# NodeMCU_AQM-4.net
KiCad netlist of a schematic drawn in EAGLE
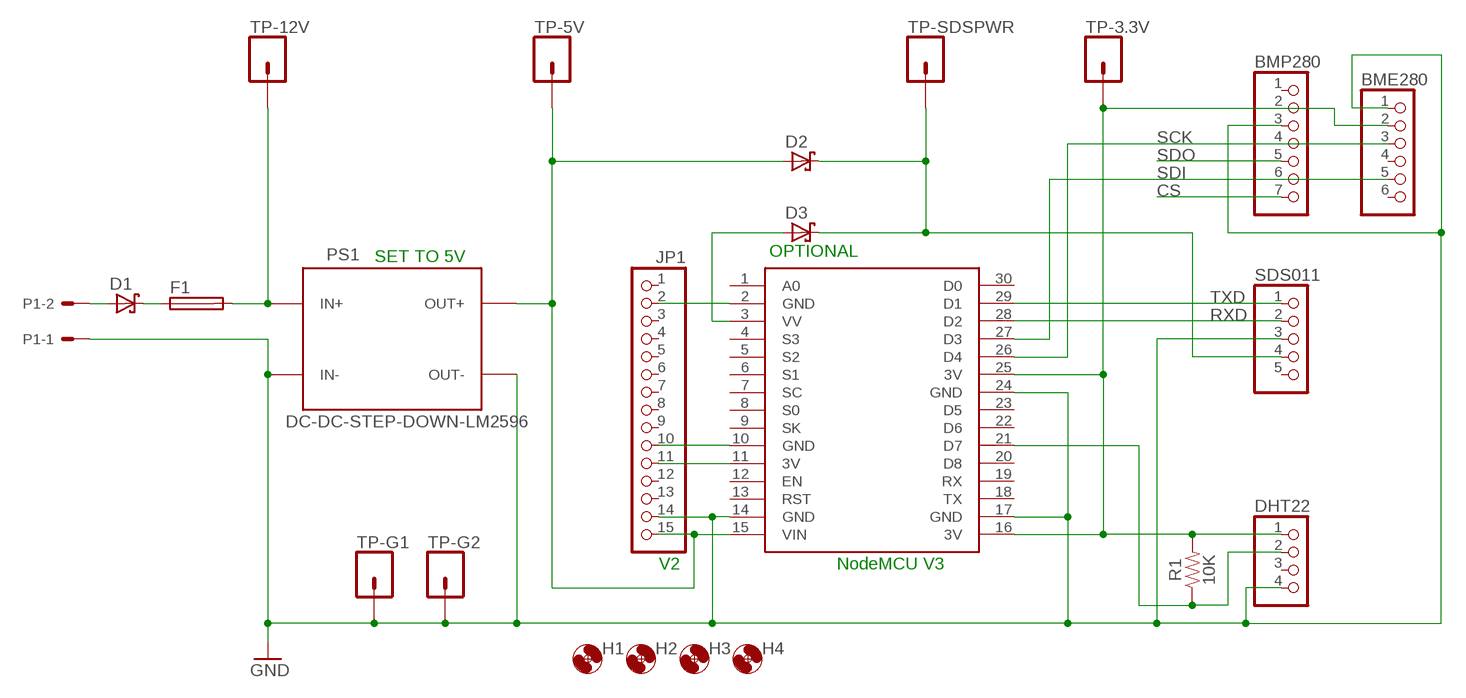
[diagram p0: schematic, sheet 1]

(export (version "E")
  (design (tool "Eeschema 10.0.6"))
  (components
    (comp (ref "BME280")
      (value "PINHD-1X6")
      (footprint "eagle-import:1X06")
      (libsource (lib "eagle-import") (part "PINHD-1X6"))
    )
    (comp (ref "BMP280")
      (value "PINHD-1X7")
      (footprint "eagle-import:1X07")
      (libsource (lib "eagle-import") (part "PINHD-1X7"))
    )
    (comp (ref "D1")
      (value "SCHOTTKY-DIODEF126Z12")
      (footprint "eagle-import:DIODE_F126Z12")
      (libsource (lib "eagle-import") (part "SCHOTTKY-DIODEF126Z12"))
    )
    (comp (ref "D2")
      (value "SCHOTTKY-DIODEF126Z12")
      (footprint "eagle-import:DIODE_F126Z12")
      (libsource (lib "eagle-import") (part "SCHOTTKY-DIODEF126Z12"))
    )
    (comp (ref "D3")
      (value "SCHOTTKY-DIODEF126Z12")
      (footprint "eagle-import:DIODE_F126Z12")
      (libsource (lib "eagle-import") (part "SCHOTTKY-DIODEF126Z12"))
    )
    (comp (ref "DHT22")
      (value "PINHD-1X4")
      (footprint "eagle-import:1X04")
      (libsource (lib "eagle-import") (part "PINHD-1X4"))
    )
    (comp (ref "F1")
      (value "SH22,5A")
      (footprint "eagle-import:SH22,5A")
      (fields (field (name "MPN") "0031.7701.11"))
      (libsource (lib "eagle-import") (part "SH22,5A"))
    )
    (comp (ref "H1")
      (value "MOUNT-HOLE3.6")
      (footprint "eagle-import:3,6")
      (libsource (lib "eagle-import") (part "MOUNT-HOLE3.6"))
    )
    (comp (ref "H2")
      (value "MOUNT-HOLE3.6")
      (footprint "eagle-import:3,6")
      (libsource (lib "eagle-import") (part "MOUNT-HOLE3.6"))
    )
    (comp (ref "H3")
      (value "MOUNT-HOLE3.6")
      (footprint "eagle-import:3,6")
      (libsource (lib "eagle-import") (part "MOUNT-HOLE3.6"))
    )
    (comp (ref "H4")
      (value "MOUNT-HOLE3.6")
      (footprint "eagle-import:3,6")
      (libsource (lib "eagle-import") (part "MOUNT-HOLE3.6"))
    )
    (comp (ref "JP1")
      (value "PINHD-1X15")
      (footprint "eagle-import:1X15")
      (libsource (lib "eagle-import") (part "PINHD-1X15"))
    )
    (comp (ref "P1")
      (value "KK-156-2")
      (footprint "eagle-import:KK-156-2")
      (fields (field (name "MF") "MOLEX"))
      (libsource (lib "eagle-import") (part "KK-156-2"))
    )
    (comp (ref "PS1")
      (value "DC-DC-STEP-DOWN-LM2596")
      (footprint "eagle-import:DC-DC-STEP-DOWN-LM2596")
      (libsource (lib "eagle-import") (part "DC-DC-STEP-DOWN-LM2596"))
    )
    (comp (ref "R1")
      (value "10K")
      (footprint "eagle-import:AXIAL-0.3")
      (libsource (lib "eagle-import") (part "1KOHM-HORIZ-1/4W-5%"))
    )
    (comp (ref "SDS011")
      (value "PINHD-1X5")
      (footprint "eagle-import:1X05")
      (libsource (lib "eagle-import") (part "PINHD-1X5"))
    )
    (comp (ref "TP-3.3V")
      (value "CONN_01OFFSET")
      (footprint "eagle-import:1X01_OFFSET")
      (libsource (lib "eagle-import") (part "CONN_01OFFSET"))
    )
    (comp (ref "TP-5V")
      (value "CONN_01OFFSET")
      (footprint "eagle-import:1X01_OFFSET")
      (libsource (lib "eagle-import") (part "CONN_01OFFSET"))
    )
    (comp (ref "TP-12V")
      (value "CONN_01OFFSET")
      (footprint "eagle-import:1X01_OFFSET")
      (libsource (lib "eagle-import") (part "CONN_01OFFSET"))
    )
    (comp (ref "TP-G1")
      (value "CONN_01OFFSET")
      (footprint "eagle-import:1X01_OFFSET")
      (libsource (lib "eagle-import") (part "CONN_01OFFSET"))
    )
    (comp (ref "TP-G2")
      (value "CONN_01OFFSET")
      (footprint "eagle-import:1X01_OFFSET")
      (libsource (lib "eagle-import") (part "CONN_01OFFSET"))
    )
    (comp (ref "TP-SDSPWR")
      (value "CONN_01OFFSET")
      (footprint "eagle-import:1X01_OFFSET")
      (libsource (lib "eagle-import") (part "CONN_01OFFSET"))
    )
    (comp (ref "U$1")
      (value "NODEMCU")
      (footprint "eagle-import:NODEMCU")
      (libsource (lib "eagle-import") (part "NODEMCU"))
    )
  )
  (nets
    (net (code "1") (name "/3V3") (class "Default")
      (node (ref "BME280") (pin "2") (pinfunction "2_2") (pintype "passive"))
      (node (ref "BMP280") (pin "2") (pinfunction "2_2") (pintype "passive"))
      (node (ref "DHT22") (pin "1") (pinfunction "1_1") (pintype "passive"))
      (node (ref "JP1") (pin "11") (pinfunction "11_11") (pintype "passive"))
      (node (ref "R1") (pin "P$2") (pinfunction "2_P$2") (pintype "passive"))
      (node (ref "TP-3.3V") (pin "1") (pinfunction "1_1") (pintype "passive"))
      (node (ref "U$1") (pin "11") (pinfunction "3V_11") (pintype "power_in"))
      (node (ref "U$1") (pin "16") (pinfunction "3V_16") (pintype "power_in"))
      (node (ref "U$1") (pin "25") (pinfunction "3V_25") (pintype "power_in"))
    )
    (net (code "2") (name "/CS") (class "Default")
      (node (ref "BMP280") (pin "7") (pinfunction "7_7") (pintype "passive"))
    )
    (net (code "3") (name "/RXD") (class "Default")
      (node (ref "SDS011") (pin "2") (pinfunction "2_2") (pintype "passive"))
      (node (ref "U$1") (pin "28") (pinfunction "D2_28") (pintype "bidirectional"))
    )
    (net (code "4") (name "/SCK") (class "Default")
      (node (ref "BME280") (pin "3") (pinfunction "3_3") (pintype "passive"))
      (node (ref "BMP280") (pin "4") (pinfunction "4_4") (pintype "passive"))
      (node (ref "U$1") (pin "26") (pinfunction "D4_26") (pintype "bidirectional"))
    )
    (net (code "5") (name "/SDI") (class "Default")
      (node (ref "BME280") (pin "5") (pinfunction "5_5") (pintype "passive"))
      (node (ref "BMP280") (pin "6") (pinfunction "6_6") (pintype "passive"))
      (node (ref "U$1") (pin "27") (pinfunction "D3_27") (pintype "bidirectional"))
    )
    (net (code "6") (name "/SDO") (class "Default")
      (node (ref "BMP280") (pin "5") (pinfunction "5_5") (pintype "passive"))
    )
    (net (code "7") (name "/TXD") (class "Default")
      (node (ref "SDS011") (pin "1") (pinfunction "1_1") (pintype "passive"))
      (node (ref "U$1") (pin "29") (pinfunction "D1_29") (pintype "bidirectional"))
    )
    (net (code "8") (name "GND") (class "Default")
      (node (ref "BME280") (pin "1") (pinfunction "1_1") (pintype "passive"))
      (node (ref "BMP280") (pin "3") (pinfunction "3_3") (pintype "passive"))
      (node (ref "DHT22") (pin "4") (pinfunction "4_4") (pintype "passive"))
      (node (ref "JP1") (pin "10") (pinfunction "10_10") (pintype "passive"))
      (node (ref "JP1") (pin "14") (pinfunction "14_14") (pintype "passive"))
      (node (ref "JP1") (pin "2") (pinfunction "2_2") (pintype "passive"))
      (node (ref "P1") (pin "1") (pinfunction "S_1") (pintype "passive"))
      (node (ref "PS1") (pin "IN-") (pinfunction "IN-_IN-") (pintype "bidirectional"))
      (node (ref "PS1") (pin "OUT-") (pinfunction "OUT-_OUT-") (pintype "bidirectional"))
      (node (ref "SDS011") (pin "3") (pinfunction "3_3") (pintype "passive"))
      (node (ref "TP-G1") (pin "1") (pinfunction "1_1") (pintype "passive"))
      (node (ref "TP-G2") (pin "1") (pinfunction "1_1") (pintype "passive"))
      (node (ref "U$1") (pin "10") (pinfunction "GND_10") (pintype "power_in"))
      (node (ref "U$1") (pin "14") (pinfunction "GND_14") (pintype "power_in"))
      (node (ref "U$1") (pin "17") (pinfunction "GND_17") (pintype "power_in"))
      (node (ref "U$1") (pin "2") (pinfunction "GND_2") (pintype "power_in"))
      (node (ref "U$1") (pin "24") (pinfunction "GND_24") (pintype "power_in"))
    )
    (net (code "9") (name "Net-(D1-A)") (class "Default")
      (node (ref "D1") (pin "C") (pinfunction "A_C") (pintype "passive"))
      (node (ref "F1") (pin "1") (pinfunction "1_1") (pintype "passive"))
    )
    (net (code "10") (name "Net-(D1-C)") (class "Default")
      (node (ref "D1") (pin "A") (pinfunction "C_A") (pintype "passive"))
      (node (ref "P1") (pin "2") (pinfunction "S_2") (pintype "passive"))
    )
    (net (code "11") (name "Net-(D2-A)") (class "Default")
      (node (ref "D2") (pin "C") (pinfunction "A_C") (pintype "passive"))
      (node (ref "D3") (pin "C") (pinfunction "A_C") (pintype "passive"))
      (node (ref "SDS011") (pin "4") (pinfunction "4_4") (pintype "passive"))
      (node (ref "TP-SDSPWR") (pin "1") (pinfunction "1_1") (pintype "passive"))
    )
    (net (code "12") (name "Net-(D2-C)") (class "Default")
      (node (ref "D2") (pin "A") (pinfunction "C_A") (pintype "passive"))
      (node (ref "JP1") (pin "15") (pinfunction "15_15") (pintype "passive"))
      (node (ref "PS1") (pin "OUT+") (pinfunction "OUT+_OUT+") (pintype "bidirectional"))
      (node (ref "TP-5V") (pin "1") (pinfunction "1_1") (pintype "passive"))
      (node (ref "U$1") (pin "15") (pinfunction "VIN_15") (pintype "bidirectional"))
    )
    (net (code "13") (name "Net-(D3-C)") (class "Default")
      (node (ref "D3") (pin "A") (pinfunction "C_A") (pintype "passive"))
      (node (ref "U$1") (pin "3") (pinfunction "VV_3") (pintype "bidirectional"))
    )
    (net (code "14") (name "Net-(F1-Pad2)") (class "Default")
      (node (ref "F1") (pin "2") (pinfunction "2_2") (pintype "passive"))
      (node (ref "PS1") (pin "IN+") (pinfunction "IN+_IN+") (pintype "bidirectional"))
      (node (ref "TP-12V") (pin "1") (pinfunction "1_1") (pintype "passive"))
    )
    (net (code "15") (name "Net-(R1-1)") (class "Default")
      (node (ref "DHT22") (pin "2") (pinfunction "2_2") (pintype "passive"))
      (node (ref "R1") (pin "P$1") (pinfunction "1_P$1") (pintype "passive"))
      (node (ref "U$1") (pin "21") (pinfunction "D7_21") (pintype "bidirectional"))
    )
    (net (code "16") (name "unconnected-(BME280-Pad4)") (class "Default")
      (node (ref "BME280") (pin "4") (pinfunction "4_4") (pintype "passive"))
    )
    (net (code "17") (name "unconnected-(BME280-Pad6)") (class "Default")
      (node (ref "BME280") (pin "6") (pinfunction "6_6") (pintype "passive"))
    )
    (net (code "18") (name "unconnected-(BMP280-Pad1)") (class "Default")
      (node (ref "BMP280") (pin "1") (pinfunction "1_1") (pintype "passive"))
    )
    (net (code "19") (name "unconnected-(DHT22-Pad3)") (class "Default")
      (node (ref "DHT22") (pin "3") (pinfunction "3_3") (pintype "passive"))
    )
    (net (code "20") (name "unconnected-(JP1-Pad1)") (class "Default")
      (node (ref "JP1") (pin "1") (pinfunction "1_1") (pintype "passive"))
    )
    (net (code "21") (name "unconnected-(JP1-Pad3)") (class "Default")
      (node (ref "JP1") (pin "3") (pinfunction "3_3") (pintype "passive"))
    )
    (net (code "22") (name "unconnected-(JP1-Pad4)") (class "Default")
      (node (ref "JP1") (pin "4") (pinfunction "4_4") (pintype "passive"))
    )
    (net (code "23") (name "unconnected-(JP1-Pad5)") (class "Default")
      (node (ref "JP1") (pin "5") (pinfunction "5_5") (pintype "passive"))
    )
    (net (code "24") (name "unconnected-(JP1-Pad6)") (class "Default")
      (node (ref "JP1") (pin "6") (pinfunction "6_6") (pintype "passive"))
    )
    (net (code "25") (name "unconnected-(JP1-Pad7)") (class "Default")
      (node (ref "JP1") (pin "7") (pinfunction "7_7") (pintype "passive"))
    )
    (net (code "26") (name "unconnected-(JP1-Pad8)") (class "Default")
      (node (ref "JP1") (pin "8") (pinfunction "8_8") (pintype "passive"))
    )
    (net (code "27") (name "unconnected-(JP1-Pad9)") (class "Default")
      (node (ref "JP1") (pin "9") (pinfunction "9_9") (pintype "passive"))
    )
    (net (code "28") (name "unconnected-(JP1-Pad12)") (class "Default")
      (node (ref "JP1") (pin "12") (pinfunction "12_12") (pintype "passive"))
    )
    (net (code "29") (name "unconnected-(JP1-Pad13)") (class "Default")
      (node (ref "JP1") (pin "13") (pinfunction "13_13") (pintype "passive"))
    )
    (net (code "30") (name "unconnected-(SDS011-Pad5)") (class "Default")
      (node (ref "SDS011") (pin "5") (pinfunction "5_5") (pintype "passive"))
    )
    (net (code "31") (name "unconnected-(U$1-A0-Pad1)") (class "Default")
      (node (ref "U$1") (pin "1") (pinfunction "A0_1") (pintype "bidirectional"))
    )
    (net (code "32") (name "unconnected-(U$1-D0-Pad30)") (class "Default")
      (node (ref "U$1") (pin "30") (pinfunction "D0_30") (pintype "bidirectional"))
    )
    (net (code "33") (name "unconnected-(U$1-D5-Pad23)") (class "Default")
      (node (ref "U$1") (pin "23") (pinfunction "D5_23") (pintype "bidirectional"))
    )
    (net (code "34") (name "unconnected-(U$1-D6-Pad22)") (class "Default")
      (node (ref "U$1") (pin "22") (pinfunction "D6_22") (pintype "bidirectional"))
    )
    (net (code "35") (name "unconnected-(U$1-D8-Pad20)") (class "Default")
      (node (ref "U$1") (pin "20") (pinfunction "D8_20") (pintype "bidirectional"))
    )
    (net (code "36") (name "unconnected-(U$1-EN-Pad12)") (class "Default")
      (node (ref "U$1") (pin "12") (pinfunction "EN_12") (pintype "bidirectional"))
    )
    (net (code "37") (name "unconnected-(U$1-RST-Pad13)") (class "Default")
      (node (ref "U$1") (pin "13") (pinfunction "RST_13") (pintype "bidirectional"))
    )
    (net (code "38") (name "unconnected-(U$1-RX-Pad19)") (class "Default")
      (node (ref "U$1") (pin "19") (pinfunction "RX_19") (pintype "bidirectional"))
    )
    (net (code "39") (name "unconnected-(U$1-S0-Pad8)") (class "Default")
      (node (ref "U$1") (pin "8") (pinfunction "S0_8") (pintype "bidirectional"))
    )
    (net (code "40") (name "unconnected-(U$1-S1-Pad6)") (class "Default")
      (node (ref "U$1") (pin "6") (pinfunction "S1_6") (pintype "bidirectional"))
    )
    (net (code "41") (name "unconnected-(U$1-S2-Pad5)") (class "Default")
      (node (ref "U$1") (pin "5") (pinfunction "S2_5") (pintype "bidirectional"))
    )
    (net (code "42") (name "unconnected-(U$1-S3-Pad4)") (class "Default")
      (node (ref "U$1") (pin "4") (pinfunction "S3_4") (pintype "bidirectional"))
    )
    (net (code "43") (name "unconnected-(U$1-SC-Pad7)") (class "Default")
      (node (ref "U$1") (pin "7") (pinfunction "SC_7") (pintype "bidirectional"))
    )
    (net (code "44") (name "unconnected-(U$1-SK-Pad9)") (class "Default")
      (node (ref "U$1") (pin "9") (pinfunction "SK_9") (pintype "bidirectional"))
    )
    (net (code "45") (name "unconnected-(U$1-TX-Pad18)") (class "Default")
      (node (ref "U$1") (pin "18") (pinfunction "TX_18") (pintype "bidirectional"))
    )
  )
)
